# WL_BPF.net
KiCad netlist of a schematic drawn in Altium Designer
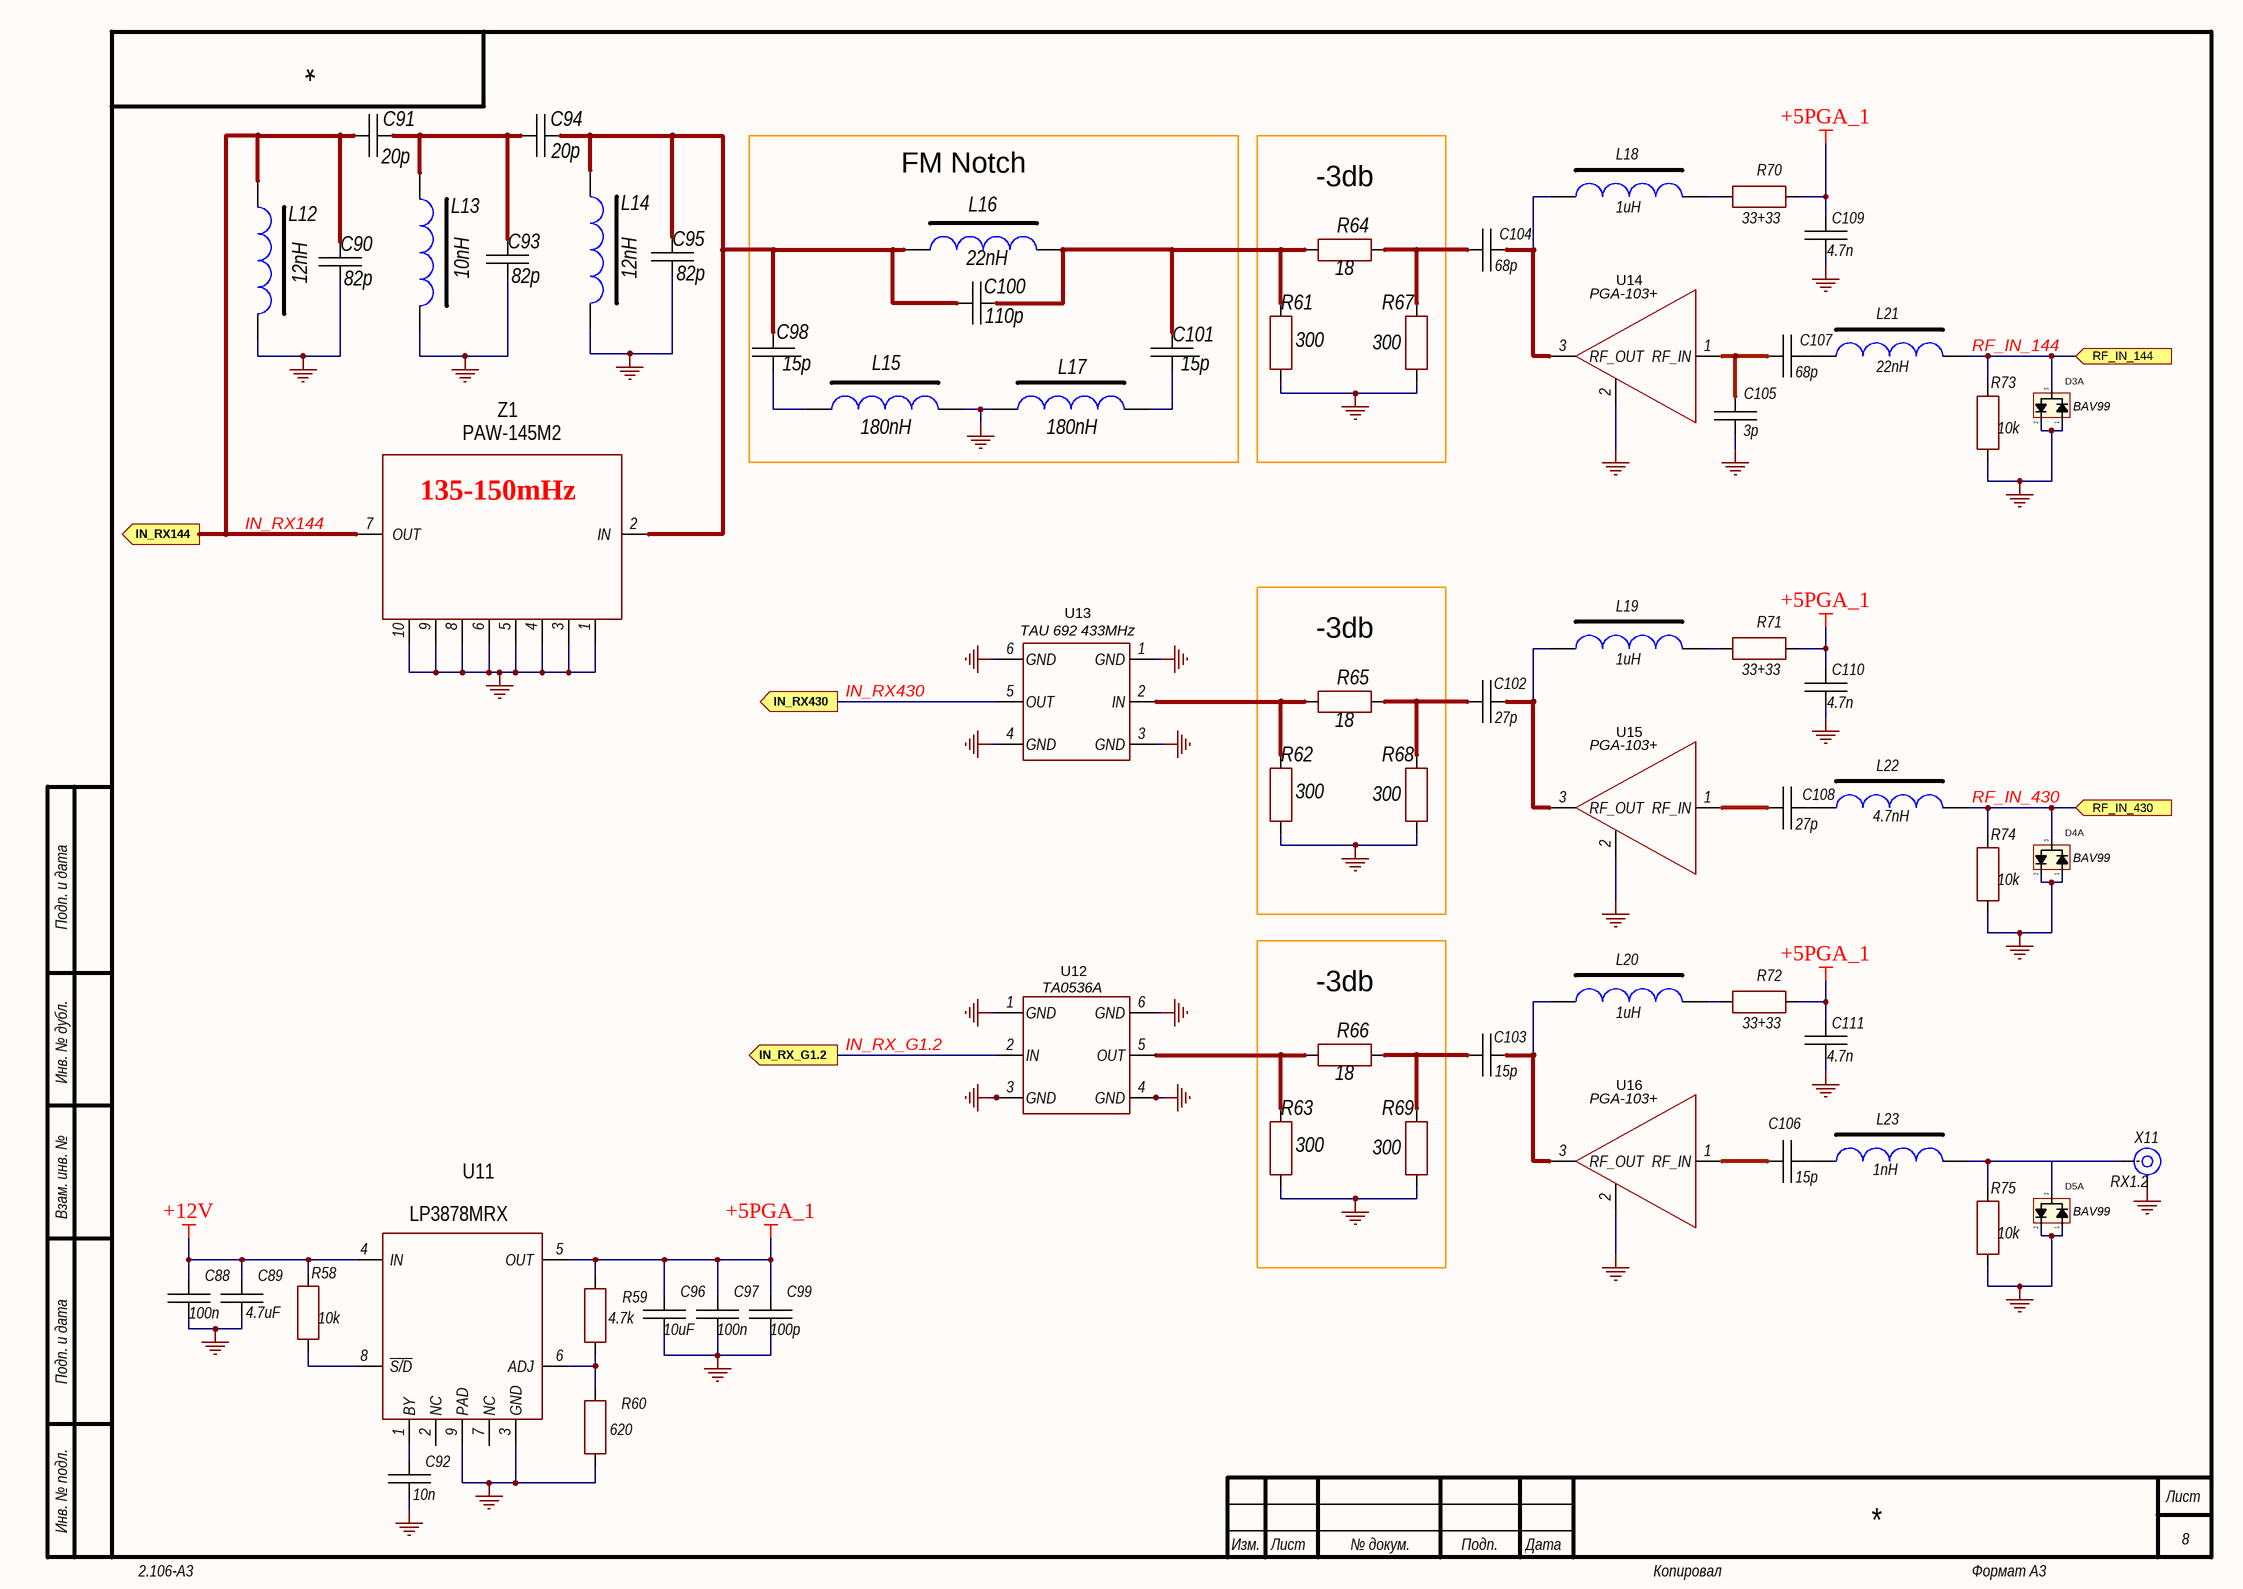
[diagram p0: WL_BPF.SchDoc]

(export (version "E")
  (design (tool "Eeschema 10.0.6"))
  (components
    (comp (ref "C88")
      (value "100n")
      (footprint "standard:CH0805C")
      (libsource (lib "Discrete") (part "Capacitor"))
    )
    (comp (ref "C89")
      (value "4.7uF")
      (footprint "standard:CH0805C")
      (libsource (lib "Discrete") (part "Capacitor"))
    )
    (comp (ref "C90")
      (value "82p")
      (footprint "standard:CH0805C")
      (libsource (lib "Discrete") (part "Capacitor"))
    )
    (comp (ref "C91")
      (value "20p")
      (footprint "standard:CH0805C")
      (libsource (lib "Discrete") (part "Capacitor"))
    )
    (comp (ref "C92")
      (value "10n")
      (footprint "standard:CH0805C")
      (libsource (lib "Discrete") (part "Capacitor"))
    )
    (comp (ref "C93")
      (value "82p")
      (footprint "standard:CH0805C")
      (libsource (lib "Discrete") (part "Capacitor"))
    )
    (comp (ref "C94")
      (value "20p")
      (footprint "standard:CH0805C")
      (libsource (lib "Discrete") (part "Capacitor"))
    )
    (comp (ref "C95")
      (value "82p")
      (footprint "standard:CH0805C")
      (libsource (lib "Discrete") (part "Capacitor"))
    )
    (comp (ref "C96")
      (value "10uF")
      (footprint "standard:CH0805C")
      (libsource (lib "Discrete") (part "Capacitor"))
    )
    (comp (ref "C97")
      (value "100n")
      (footprint "standard:CH0805C")
      (libsource (lib "Discrete") (part "Capacitor"))
    )
    (comp (ref "C98")
      (value "15p")
      (footprint "standard:CH0805C")
      (libsource (lib "Discrete") (part "Capacitor"))
    )
    (comp (ref "C99")
      (value "100p")
      (footprint "standard:CH0805C")
      (libsource (lib "Discrete") (part "Capacitor"))
    )
    (comp (ref "C100")
      (value "110p")
      (footprint "standard:CH0805C")
      (libsource (lib "Discrete") (part "Capacitor"))
    )
    (comp (ref "C101")
      (value "15p")
      (footprint "standard:CH0805C")
      (libsource (lib "Discrete") (part "Capacitor"))
    )
    (comp (ref "C102")
      (value "27p")
      (footprint "standard:CH0805C")
      (libsource (lib "Discrete") (part "Capacitor"))
    )
    (comp (ref "C103")
      (value "15p")
      (footprint "standard:CH0603C")
      (libsource (lib "Discrete") (part "Capacitor"))
    )
    (comp (ref "C104")
      (value "68p")
      (footprint "standard:CH0805C")
      (libsource (lib "Discrete") (part "Capacitor"))
    )
    (comp (ref "C105")
      (value "3p")
      (footprint "standard:CH0805C")
      (libsource (lib "Discrete") (part "Capacitor"))
    )
    (comp (ref "C106")
      (value "15p")
      (footprint "standard:CH0603C")
      (libsource (lib "Discrete") (part "Capacitor"))
    )
    (comp (ref "C107")
      (value "68p")
      (footprint "standard:CH0805C")
      (libsource (lib "Discrete") (part "Capacitor"))
    )
    (comp (ref "C108")
      (value "27p")
      (footprint "standard:CH0805C")
      (libsource (lib "Discrete") (part "Capacitor"))
    )
    (comp (ref "C109")
      (value "4.7n")
      (footprint "standard:CH0805C")
      (libsource (lib "Discrete") (part "Capacitor"))
    )
    (comp (ref "C110")
      (value "4.7n")
      (footprint "standard:CH0805C")
      (libsource (lib "Discrete") (part "Capacitor"))
    )
    (comp (ref "C111")
      (value "4.7n")
      (footprint "standard:CH0805C")
      (libsource (lib "Discrete") (part "Capacitor"))
    )
    (comp (ref "D3") (value "BAV99") (footprint "SOT23_132") (libsource (lib "Analog") (part "BAV99")))
    (comp (ref "D4") (value "BAV99") (footprint "SOT23_132") (libsource (lib "Analog") (part "BAV99")))
    (comp (ref "D5") (value "BAV99") (footprint "SOT23_132") (libsource (lib "Analog") (part "BAV99")))
    (comp (ref "L12") (value "12nH") (footprint "L1210") (libsource (lib "") (part "TRANS_1")))
    (comp (ref "L13") (value "10nH") (footprint "L1210") (libsource (lib "") (part "TRANS_1")))
    (comp (ref "L14") (value "12nH") (footprint "L1210") (libsource (lib "") (part "TRANS_1")))
    (comp (ref "L15") (value "180nH") (footprint "L1210") (libsource (lib "") (part "TRANS_1")))
    (comp (ref "L16") (value "22nH") (footprint "L1210") (libsource (lib "") (part "TRANS_1")))
    (comp (ref "L17") (value "180nH") (footprint "L1210") (libsource (lib "") (part "TRANS_1")))
    (comp (ref "L18") (value "1uH") (footprint "L1210") (libsource (lib "Transformers") (part "TRANS")))
    (comp (ref "L19") (value "1uH") (footprint "L1210") (libsource (lib "Transformers") (part "TRANS")))
    (comp (ref "L20") (value "1uH") (footprint "L1210") (libsource (lib "Transformers") (part "TRANS")))
    (comp (ref "L21") (value "22nH") (footprint "L1210") (libsource (lib "Transformers") (part "TRANS")))
    (comp (ref "L22") (value "4.7nH") (footprint "L1210") (libsource (lib "Transformers") (part "TRANS")))
    (comp (ref "L23") (value "1nH") (footprint "L1210") (libsource (lib "Transformers") (part "TRANS")))
    (comp (ref "R58") (value "10k") (footprint "standard:CH0805R") (libsource (lib "") (part "Resistor_2")))
    (comp (ref "R59") (value "4.7k") (footprint "standard:CH0805R") (libsource (lib "") (part "Resistor_2")))
    (comp (ref "R60") (value "620") (footprint "standard:CH0805R") (libsource (lib "") (part "Resistor_2")))
    (comp (ref "R61")
      (value "300")
      (footprint "standard:CH0805R")
      (libsource (lib "Discrete") (part "Resistor"))
    )
    (comp (ref "R62")
      (value "300")
      (footprint "standard:CH0805R")
      (libsource (lib "Discrete") (part "Resistor"))
    )
    (comp (ref "R63")
      (value "300")
      (footprint "standard:CH0603R")
      (libsource (lib "Discrete") (part "Resistor"))
    )
    (comp (ref "R64") (value "18") (footprint "standard:CH0805R") (libsource (lib "") (part "Resistor_1")))
    (comp (ref "R65") (value "18") (footprint "standard:CH0805R") (libsource (lib "") (part "Resistor_1")))
    (comp (ref "R66") (value "18") (footprint "standard:CH0603R") (libsource (lib "") (part "Resistor_1")))
    (comp (ref "R67")
      (value "300")
      (footprint "standard:CH0805R")
      (libsource (lib "Discrete") (part "Resistor"))
    )
    (comp (ref "R68")
      (value "300")
      (footprint "standard:CH0805R")
      (libsource (lib "Discrete") (part "Resistor"))
    )
    (comp (ref "R69")
      (value "300")
      (footprint "standard:CH0603R")
      (libsource (lib "Discrete") (part "Resistor"))
    )
    (comp (ref "R70") (value "33+33") (footprint "WL_RFFC:CH1206R") (libsource (lib "") (part "Resistor_3")))
    (comp (ref "R71") (value "33+33") (footprint "WL_RFFC:CH1206R") (libsource (lib "") (part "Resistor_3")))
    (comp (ref "R72") (value "33+33") (footprint "WL_RFFC:CH1206R") (libsource (lib "") (part "Resistor_3")))
    (comp (ref "R73") (value "10k") (footprint "standard:CH0805R") (libsource (lib "") (part "Resistor_2")))
    (comp (ref "R74") (value "10k") (footprint "standard:CH0805R") (libsource (lib "") (part "Resistor_2")))
    (comp (ref "R75") (value "10k") (footprint "standard:CH0805R") (libsource (lib "") (part "Resistor_4")))
    (comp (ref "U11")
      (value "LP3878MRX")
      (footprint "8-SOIC (PAD)")
      (libsource (lib "Power Supplies") (part "LP3878"))
    )
    (comp (ref "U12") (value "TA0536A") (footprint "MA08803") (libsource (lib "Digital") (part "TAU692")))
    (comp (ref "U13") (value "TAU 692 433MHz") (footprint "TAU692") (libsource (lib "") (part "TAU692_1")))
    (comp (ref "U14")
      (value "PGA-103+")
      (footprint "SOT89_123")
      (libsource (lib "Digital") (part "PGA-103+"))
    )
    (comp (ref "U15")
      (value "PGA-103+")
      (footprint "SOT89_123")
      (libsource (lib "Digital") (part "PGA-103+"))
    )
    (comp (ref "U16")
      (value "PGA-103+")
      (footprint "SOT89_123")
      (libsource (lib "Digital") (part "PGA-103+"))
    )
    (comp (ref "X11")
      (value "RX1.2")
      (footprint "CON: u.Fl")
      (description "RF")
      (libsource (lib "Connectors") (part "SMA"))
    )
    (comp (ref "Z1") (value "PAW-145M2") (footprint "PAV") (libsource (lib "Module") (part "SXBP_PAW")))
  )
  (nets
    (net (code "1") (name "+5PGA_1") (class "Default")
      (node (ref "C109") (pin "2") (pinfunction "2_2") (pintype "passive"))
      (node (ref "C110") (pin "2") (pinfunction "2_2") (pintype "passive"))
      (node (ref "C111") (pin "2") (pinfunction "2_2") (pintype "passive"))
      (node (ref "C96") (pin "2") (pinfunction "2_2") (pintype "passive"))
      (node (ref "C97") (pin "2") (pinfunction "2_2") (pintype "passive"))
      (node (ref "C99") (pin "2") (pinfunction "2_2") (pintype "passive"))
      (node (ref "R59") (pin "2") (pinfunction "2_2") (pintype "passive"))
      (node (ref "R70") (pin "2") (pinfunction "2_2") (pintype "passive"))
      (node (ref "R71") (pin "2") (pinfunction "2_2") (pintype "passive"))
      (node (ref "R72") (pin "2") (pinfunction "2_2") (pintype "passive"))
      (node (ref "U11") (pin "5") (pinfunction "OUT_5") (pintype "power_in"))
    )
    (net (code "2") (name "+12V") (class "Default")
      (node (ref "C88") (pin "2") (pinfunction "2_2") (pintype "passive"))
      (node (ref "C89") (pin "2") (pinfunction "2_2") (pintype "passive"))
      (node (ref "R58") (pin "2") (pinfunction "2_2") (pintype "passive"))
      (node (ref "U11") (pin "4") (pinfunction "IN_4") (pintype "power_in"))
    )
    (net (code "3") (name "/IN_RX144") (class "Default")
      (node (ref "C90") (pin "2") (pinfunction "2_2") (pintype "passive"))
      (node (ref "C91") (pin "2") (pinfunction "2_2") (pintype "passive"))
      (node (ref "L12") (pin "1") (pinfunction "1_1") (pintype "passive"))
      (node (ref "Z1") (pin "7") (pinfunction "OUT_7") (pintype "passive"))
    )
    (net (code "4") (name "/IN_RX430") (class "Default")
      (node (ref "U13") (pin "5") (pinfunction "OUT_5") (pintype "passive"))
    )
    (net (code "5") (name "/IN_RX_G1.2") (class "Default")
      (node (ref "U12") (pin "2") (pinfunction "IN_2") (pintype "passive"))
    )
    (net (code "6") (name "/RF_IN_144") (class "Default")
      (node (ref "D3") (pin "3") (pinfunction "9_3") (pintype "passive"))
      (node (ref "L21") (pin "1") (pinfunction "1_1") (pintype "power_in"))
      (node (ref "R73") (pin "2") (pinfunction "2_2") (pintype "passive"))
    )
    (net (code "7") (name "/RF_IN_430") (class "Default")
      (node (ref "D4") (pin "3") (pinfunction "9_3") (pintype "passive"))
      (node (ref "L22") (pin "1") (pinfunction "1_1") (pintype "power_in"))
      (node (ref "R74") (pin "2") (pinfunction "2_2") (pintype "passive"))
    )
    (net (code "8") (name "GND") (class "Default")
      (node (ref "C105") (pin "1") (pinfunction "1_1") (pintype "passive"))
      (node (ref "C109") (pin "1") (pinfunction "1_1") (pintype "passive"))
      (node (ref "C110") (pin "1") (pinfunction "1_1") (pintype "passive"))
      (node (ref "C111") (pin "1") (pinfunction "1_1") (pintype "passive"))
      (node (ref "C88") (pin "1") (pinfunction "1_1") (pintype "passive"))
      (node (ref "C89") (pin "1") (pinfunction "1_1") (pintype "passive"))
      (node (ref "C90") (pin "1") (pinfunction "1_1") (pintype "passive"))
      (node (ref "C92") (pin "1") (pinfunction "1_1") (pintype "passive"))
      (node (ref "C93") (pin "1") (pinfunction "1_1") (pintype "passive"))
      (node (ref "C95") (pin "1") (pinfunction "1_1") (pintype "passive"))
      (node (ref "C96") (pin "1") (pinfunction "1_1") (pintype "passive"))
      (node (ref "C97") (pin "1") (pinfunction "1_1") (pintype "passive"))
      (node (ref "C99") (pin "1") (pinfunction "1_1") (pintype "passive"))
      (node (ref "D3") (pin "1") (pinfunction "11_1") (pintype "passive"))
      (node (ref "D3") (pin "2") (pinfunction "10_2") (pintype "passive"))
      (node (ref "D4") (pin "1") (pinfunction "11_1") (pintype "passive"))
      (node (ref "D4") (pin "2") (pinfunction "10_2") (pintype "passive"))
      (node (ref "D5") (pin "1") (pinfunction "11_1") (pintype "passive"))
      (node (ref "D5") (pin "2") (pinfunction "10_2") (pintype "passive"))
      (node (ref "L12") (pin "2") (pinfunction "2_2") (pintype "passive"))
      (node (ref "L13") (pin "2") (pinfunction "2_2") (pintype "passive"))
      (node (ref "L14") (pin "2") (pinfunction "2_2") (pintype "passive"))
      (node (ref "L15") (pin "2") (pinfunction "2_2") (pintype "passive"))
      (node (ref "L17") (pin "1") (pinfunction "1_1") (pintype "passive"))
      (node (ref "R60") (pin "1") (pinfunction "1_1") (pintype "passive"))
      (node (ref "R61") (pin "2") (pinfunction "2_2") (pintype "passive"))
      (node (ref "R62") (pin "2") (pinfunction "2_2") (pintype "passive"))
      (node (ref "R63") (pin "2") (pinfunction "2_2") (pintype "passive"))
      (node (ref "R67") (pin "2") (pinfunction "2_2") (pintype "passive"))
      (node (ref "R68") (pin "2") (pinfunction "2_2") (pintype "passive"))
      (node (ref "R69") (pin "2") (pinfunction "2_2") (pintype "passive"))
      (node (ref "R73") (pin "1") (pinfunction "1_1") (pintype "passive"))
      (node (ref "R74") (pin "1") (pinfunction "1_1") (pintype "passive"))
      (node (ref "R75") (pin "1") (pinfunction "1_1") (pintype "passive"))
      (node (ref "U11") (pin "3") (pinfunction "GND_3") (pintype "passive"))
      (node (ref "U11") (pin "9") (pinfunction "PAD_9") (pintype "passive"))
      (node (ref "U12") (pin "1") (pinfunction "GND_1") (pintype "passive"))
      (node (ref "U12") (pin "3") (pinfunction "GND_3") (pintype "passive"))
      (node (ref "U12") (pin "4") (pinfunction "GND_4") (pintype "passive"))
      (node (ref "U12") (pin "6") (pinfunction "GND_6") (pintype "passive"))
      (node (ref "U13") (pin "1") (pinfunction "GND_1") (pintype "passive"))
      (node (ref "U13") (pin "3") (pinfunction "GND_3") (pintype "passive"))
      (node (ref "U13") (pin "4") (pinfunction "GND_4") (pintype "passive"))
      (node (ref "U13") (pin "6") (pinfunction "GND_6") (pintype "passive"))
      (node (ref "U14") (pin "2") (pinfunction "GND_2") (pintype "passive"))
      (node (ref "U15") (pin "2") (pinfunction "GND_2") (pintype "passive"))
      (node (ref "U16") (pin "2") (pinfunction "GND_2") (pintype "passive"))
      (node (ref "X11") (pin "2") (pinfunction "IN_2") (pintype "passive"))
      (node (ref "Z1") (pin "1") (pinfunction "RESET_1") (pintype "passive"))
      (node (ref "Z1") (pin "10") (pinfunction "TXD_10") (pintype "passive"))
      (node (ref "Z1") (pin "3") (pinfunction "CH_PD_3") (pintype "passive"))
      (node (ref "Z1") (pin "4") (pinfunction "GPIO16_4") (pintype "passive"))
      (node (ref "Z1") (pin "5") (pinfunction "GPIO14_5") (pintype "passive"))
      (node (ref "Z1") (pin "6") (pinfunction "GPIO0_6") (pintype "passive"))
      (node (ref "Z1") (pin "8") (pinfunction "GPIO5_8") (pintype "passive"))
      (node (ref "Z1") (pin "9") (pinfunction "RXD_9") (pintype "passive"))
    )
    (net (code "9") (name "Net-(C91-Pad1)") (class "Default")
      (node (ref "C91") (pin "1") (pinfunction "1_1") (pintype "passive"))
      (node (ref "C93") (pin "2") (pinfunction "2_2") (pintype "passive"))
      (node (ref "C94") (pin "2") (pinfunction "2_2") (pintype "passive"))
      (node (ref "L13") (pin "1") (pinfunction "1_1") (pintype "passive"))
    )
    (net (code "10") (name "Net-(C98-Pad1)") (class "Default")
      (node (ref "C98") (pin "1") (pinfunction "1_1") (pintype "passive"))
      (node (ref "L15") (pin "1") (pinfunction "1_1") (pintype "passive"))
    )
    (net (code "11") (name "Net-(C100-Pad2)") (class "Default")
      (node (ref "C100") (pin "2") (pinfunction "2_2") (pintype "passive"))
      (node (ref "C101") (pin "2") (pinfunction "2_2") (pintype "passive"))
      (node (ref "L16") (pin "2") (pinfunction "2_2") (pintype "passive"))
      (node (ref "R61") (pin "1") (pinfunction "1_1") (pintype "passive"))
      (node (ref "R64") (pin "2") (pinfunction "2_2") (pintype "passive"))
    )
    (net (code "12") (name "Net-(C101-Pad1)") (class "Default")
      (node (ref "C101") (pin "1") (pinfunction "1_1") (pintype "passive"))
      (node (ref "L17") (pin "2") (pinfunction "2_2") (pintype "passive"))
    )
    (net (code "13") (name "Net-(C102-Pad1)") (class "Default")
      (node (ref "C102") (pin "1") (pinfunction "1_1") (pintype "passive"))
      (node (ref "R65") (pin "1") (pinfunction "1_1") (pintype "passive"))
      (node (ref "R68") (pin "1") (pinfunction "1_1") (pintype "passive"))
    )
    (net (code "14") (name "Net-(C103-Pad1)") (class "Default")
      (node (ref "C103") (pin "1") (pinfunction "1_1") (pintype "passive"))
      (node (ref "R66") (pin "1") (pinfunction "1_1") (pintype "passive"))
      (node (ref "R69") (pin "1") (pinfunction "1_1") (pintype "passive"))
    )
    (net (code "15") (name "Net-(C104-Pad1)") (class "Default")
      (node (ref "C104") (pin "1") (pinfunction "1_1") (pintype "passive"))
      (node (ref "R64") (pin "1") (pinfunction "1_1") (pintype "passive"))
      (node (ref "R67") (pin "1") (pinfunction "1_1") (pintype "passive"))
    )
    (net (code "16") (name "Net-(C106-Pad2)") (class "Default")
      (node (ref "C106") (pin "2") (pinfunction "2_2") (pintype "passive"))
      (node (ref "L23") (pin "2") (pinfunction "2_2") (pintype "power_in"))
    )
    (net (code "17") (name "Net-(C107-Pad2)") (class "Default")
      (node (ref "C107") (pin "2") (pinfunction "2_2") (pintype "passive"))
      (node (ref "L21") (pin "2") (pinfunction "2_2") (pintype "power_in"))
    )
    (net (code "18") (name "Net-(C108-Pad2)") (class "Default")
      (node (ref "C108") (pin "2") (pinfunction "2_2") (pintype "passive"))
      (node (ref "L22") (pin "2") (pinfunction "2_2") (pintype "power_in"))
    )
    (net (code "19") (name "Net-(D5A-9)") (class "Default")
      (node (ref "D5") (pin "3") (pinfunction "9_3") (pintype "passive"))
      (node (ref "L23") (pin "1") (pinfunction "1_1") (pintype "power_in"))
      (node (ref "R75") (pin "2") (pinfunction "2_2") (pintype "passive"))
      (node (ref "X11") (pin "1") (pinfunction "IN_1") (pintype "passive"))
    )
    (net (code "20") (name "Net-(L18-Pad1)") (class "Default")
      (node (ref "L18") (pin "1") (pinfunction "1_1") (pintype "power_in"))
      (node (ref "R70") (pin "1") (pinfunction "1_1") (pintype "passive"))
    )
    (net (code "21") (name "Net-(L19-Pad1)") (class "Default")
      (node (ref "L19") (pin "1") (pinfunction "1_1") (pintype "power_in"))
      (node (ref "R71") (pin "1") (pinfunction "1_1") (pintype "passive"))
    )
    (net (code "22") (name "Net-(L20-Pad1)") (class "Default")
      (node (ref "L20") (pin "1") (pinfunction "1_1") (pintype "power_in"))
      (node (ref "R72") (pin "1") (pinfunction "1_1") (pintype "passive"))
    )
    (net (code "23") (name "Net-(U11-ADJ)") (class "Default")
      (node (ref "R59") (pin "1") (pinfunction "1_1") (pintype "passive"))
      (node (ref "R60") (pin "2") (pinfunction "2_2") (pintype "passive"))
      (node (ref "U11") (pin "6") (pinfunction "ADJ_6") (pintype "passive"))
    )
    (net (code "24") (name "Net-(U11-BY)") (class "Default")
      (node (ref "C92") (pin "2") (pinfunction "2_2") (pintype "passive"))
      (node (ref "U11") (pin "1") (pinfunction "BY_1") (pintype "passive"))
    )
    (net (code "25") (name "Net-(U11-~{S{slash}D})") (class "Default")
      (node (ref "R58") (pin "1") (pinfunction "1_1") (pintype "passive"))
      (node (ref "U11") (pin "8") (pinfunction "~{S/D}_8") (pintype "power_in"))
    )
    (net (code "26") (name "Net-(U12-OUT)") (class "Default")
      (node (ref "R63") (pin "1") (pinfunction "1_1") (pintype "passive"))
      (node (ref "R66") (pin "2") (pinfunction "2_2") (pintype "passive"))
      (node (ref "U12") (pin "5") (pinfunction "OUT_5") (pintype "passive"))
    )
    (net (code "27") (name "Net-(U13-IN)") (class "Default")
      (node (ref "R62") (pin "1") (pinfunction "1_1") (pintype "passive"))
      (node (ref "R65") (pin "2") (pinfunction "2_2") (pintype "passive"))
      (node (ref "U13") (pin "2") (pinfunction "IN_2") (pintype "passive"))
    )
    (net (code "28") (name "Net-(U14-RF_IN)") (class "Default")
      (node (ref "C105") (pin "2") (pinfunction "2_2") (pintype "passive"))
      (node (ref "C107") (pin "1") (pinfunction "1_1") (pintype "passive"))
      (node (ref "U14") (pin "1") (pinfunction "RF_IN_1") (pintype "passive"))
    )
    (net (code "29") (name "Net-(U14-RF_OUT)") (class "Default")
      (node (ref "C104") (pin "2") (pinfunction "2_2") (pintype "passive"))
      (node (ref "L18") (pin "2") (pinfunction "2_2") (pintype "power_in"))
      (node (ref "U14") (pin "3") (pinfunction "RF_OUT_3") (pintype "passive"))
    )
    (net (code "30") (name "Net-(U15-RF_IN)") (class "Default")
      (node (ref "C108") (pin "1") (pinfunction "1_1") (pintype "passive"))
      (node (ref "U15") (pin "1") (pinfunction "RF_IN_1") (pintype "passive"))
    )
    (net (code "31") (name "Net-(U15-RF_OUT)") (class "Default")
      (node (ref "C102") (pin "2") (pinfunction "2_2") (pintype "passive"))
      (node (ref "L19") (pin "2") (pinfunction "2_2") (pintype "power_in"))
      (node (ref "U15") (pin "3") (pinfunction "RF_OUT_3") (pintype "passive"))
    )
    (net (code "32") (name "Net-(U16-RF_IN)") (class "Default")
      (node (ref "C106") (pin "1") (pinfunction "1_1") (pintype "passive"))
      (node (ref "U16") (pin "1") (pinfunction "RF_IN_1") (pintype "passive"))
    )
    (net (code "33") (name "Net-(U16-RF_OUT)") (class "Default")
      (node (ref "C103") (pin "2") (pinfunction "2_2") (pintype "passive"))
      (node (ref "L20") (pin "2") (pinfunction "2_2") (pintype "power_in"))
      (node (ref "U16") (pin "3") (pinfunction "RF_OUT_3") (pintype "passive"))
    )
    (net (code "34") (name "Net-(Z1-IN)") (class "Default")
      (node (ref "C100") (pin "1") (pinfunction "1_1") (pintype "passive"))
      (node (ref "C94") (pin "1") (pinfunction "1_1") (pintype "passive"))
      (node (ref "C95") (pin "2") (pinfunction "2_2") (pintype "passive"))
      (node (ref "C98") (pin "2") (pinfunction "2_2") (pintype "passive"))
      (node (ref "L14") (pin "1") (pinfunction "1_1") (pintype "passive"))
      (node (ref "L16") (pin "1") (pinfunction "1_1") (pintype "passive"))
      (node (ref "Z1") (pin "2") (pinfunction "IN_2") (pintype "passive"))
    )
    (net (code "35") (name "unconnected-(U11-NC-Pad2)") (class "Default")
      (node (ref "U11") (pin "2") (pinfunction "NC_2") (pintype "passive"))
    )
    (net (code "36") (name "unconnected-(U11-NC-Pad7)") (class "Default")
      (node (ref "U11") (pin "7") (pinfunction "NC_7") (pintype "passive"))
    )
  )
)
